# USB-Socket.net
KiCad netlist of a schematic drawn in Altium Designer
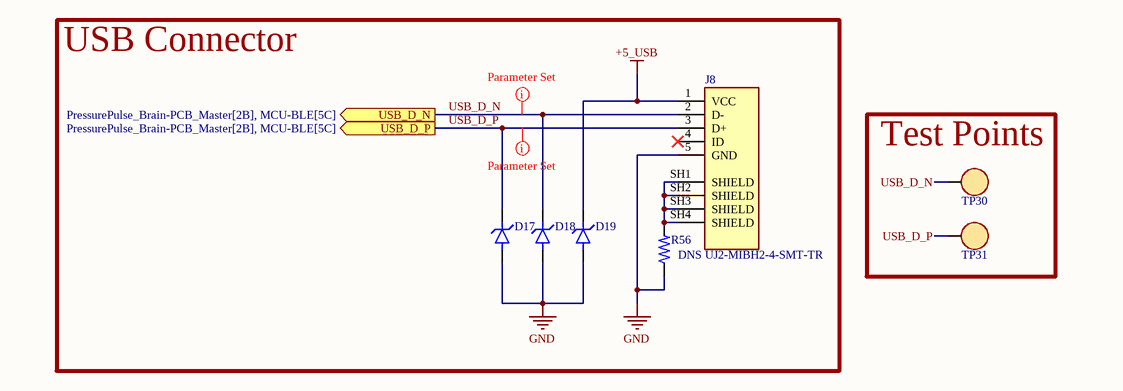
[diagram p0: USB-Socket.SchDoc]

(export (version "E")
  (design (tool "Eeschema 10.0.6"))
  (components
    (comp (ref "D17")
      (value "RCLAMP0521P.TCT")
      (footprint "PressurePulse:BDFN2C051V40")
      (description "25V Clamp 4A (8/20µs) Ipp Tvs Diode Surface Mount SLP1006P2")
      (fields (field (name "MFR") "BORN"))
      (libsource (lib "PressurePulse") (part "TVS DIODE"))
    )
    (comp (ref "D18")
      (value "RCLAMP0521P.TCT")
      (footprint "PressurePulse:BDFN2C051V40")
      (description "25V Clamp 4A (8/20µs) Ipp Tvs Diode Surface Mount SLP1006P2")
      (fields (field (name "MFR") "BORN"))
      (libsource (lib "PressurePulse") (part "TVS DIODE"))
    )
    (comp (ref "D19")
      (value "RCLAMP0521P.TCT")
      (footprint "PressurePulse:BDFN2C051V40")
      (description "25V Clamp 4A (8/20µs) Ipp Tvs Diode Surface Mount SLP1006P2")
      (fields (field (name "MFR") "BORN"))
      (libsource (lib "PressurePulse") (part "TVS DIODE"))
    )
    (comp (ref "J8")
      (value "UJ2-MIBH2-4-SMT-TR")
      (footprint "PressurePulse:USB MICRO JLC")
      (description "Micro B, USB 2.0, 1.8 A, Right Angle, Surface Mount (SMT), USB Receptacle")
      (fields (field (name "MFR") "CUI Devices"))
      (libsource (lib "PressurePulse") (part "Micro USB Port"))
    )
    (comp (ref "R56")
      (value "DNS")
      (footprint "PressurePulse:0402R")
      (description "Resistor")
      (fields (field (name "Comment") "RES"))
      (libsource (lib "PressurePulse") (part "RES"))
    )
    (comp (ref "TP30")
      (value "RH-5019")
      (footprint "PressurePulse:TP - RH-5019")
      (fields (field (name "MFR") "ronghe"))
      (libsource (lib "PressurePulse") (part "TEST POINT"))
    )
    (comp (ref "TP31")
      (value "RH-5019")
      (footprint "PressurePulse:TP - RH-5019")
      (fields (field (name "MFR") "ronghe"))
      (libsource (lib "PressurePulse") (part "TEST POINT"))
    )
  )
  (nets
    (net (code "1") (name "+5_USB") (class "Default")
      (node (ref "D19") (pin "K") (pinfunction "K_K") (pintype "passive"))
      (node (ref "J8") (pin "1") (pinfunction "VCC_1") (pintype "passive"))
    )
    (net (code "2") (name "/USB_D_N") (class "Default")
      (node (ref "D18") (pin "K") (pinfunction "K_K") (pintype "passive"))
      (node (ref "J8") (pin "2") (pinfunction "D-_2") (pintype "passive"))
      (node (ref "TP30") (pin "1") (pinfunction "1_1") (pintype "passive"))
    )
    (net (code "3") (name "/USB_D_P") (class "Default")
      (node (ref "D17") (pin "K") (pinfunction "K_K") (pintype "passive"))
      (node (ref "J8") (pin "3") (pinfunction "D+_3") (pintype "passive"))
      (node (ref "TP31") (pin "1") (pinfunction "1_1") (pintype "passive"))
    )
    (net (code "4") (name "GND") (class "Default")
      (node (ref "D17") (pin "A") (pinfunction "A_A") (pintype "passive"))
      (node (ref "D18") (pin "A") (pinfunction "A_A") (pintype "passive"))
      (node (ref "D19") (pin "A") (pinfunction "A_A") (pintype "passive"))
      (node (ref "J8") (pin "5") (pinfunction "GND_5") (pintype "passive"))
      (node (ref "R56") (pin "1") (pinfunction "1_1") (pintype "passive"))
    )
    (net (code "5") (name "Net-(J8-SHIELD-PadSH1)") (class "Default")
      (node (ref "J8") (pin "SH1") (pinfunction "SHIELD_SH1") (pintype "passive"))
      (node (ref "J8") (pin "SH2") (pinfunction "SHIELD_SH2") (pintype "passive"))
      (node (ref "J8") (pin "SH3") (pinfunction "SHIELD_SH3") (pintype "passive"))
      (node (ref "J8") (pin "SH4") (pinfunction "SHIELD_SH4") (pintype "passive"))
      (node (ref "R56") (pin "2") (pinfunction "2_2") (pintype "passive"))
    )
    (net (code "6") (name "unconnected-(J8-ID-Pad4)") (class "Default")
      (node (ref "J8") (pin "4") (pinfunction "ID_4") (pintype "passive+no_connect"))
    )
  )
)
